# PKD.net
KiCad netlist of a schematic drawn in EAGLE
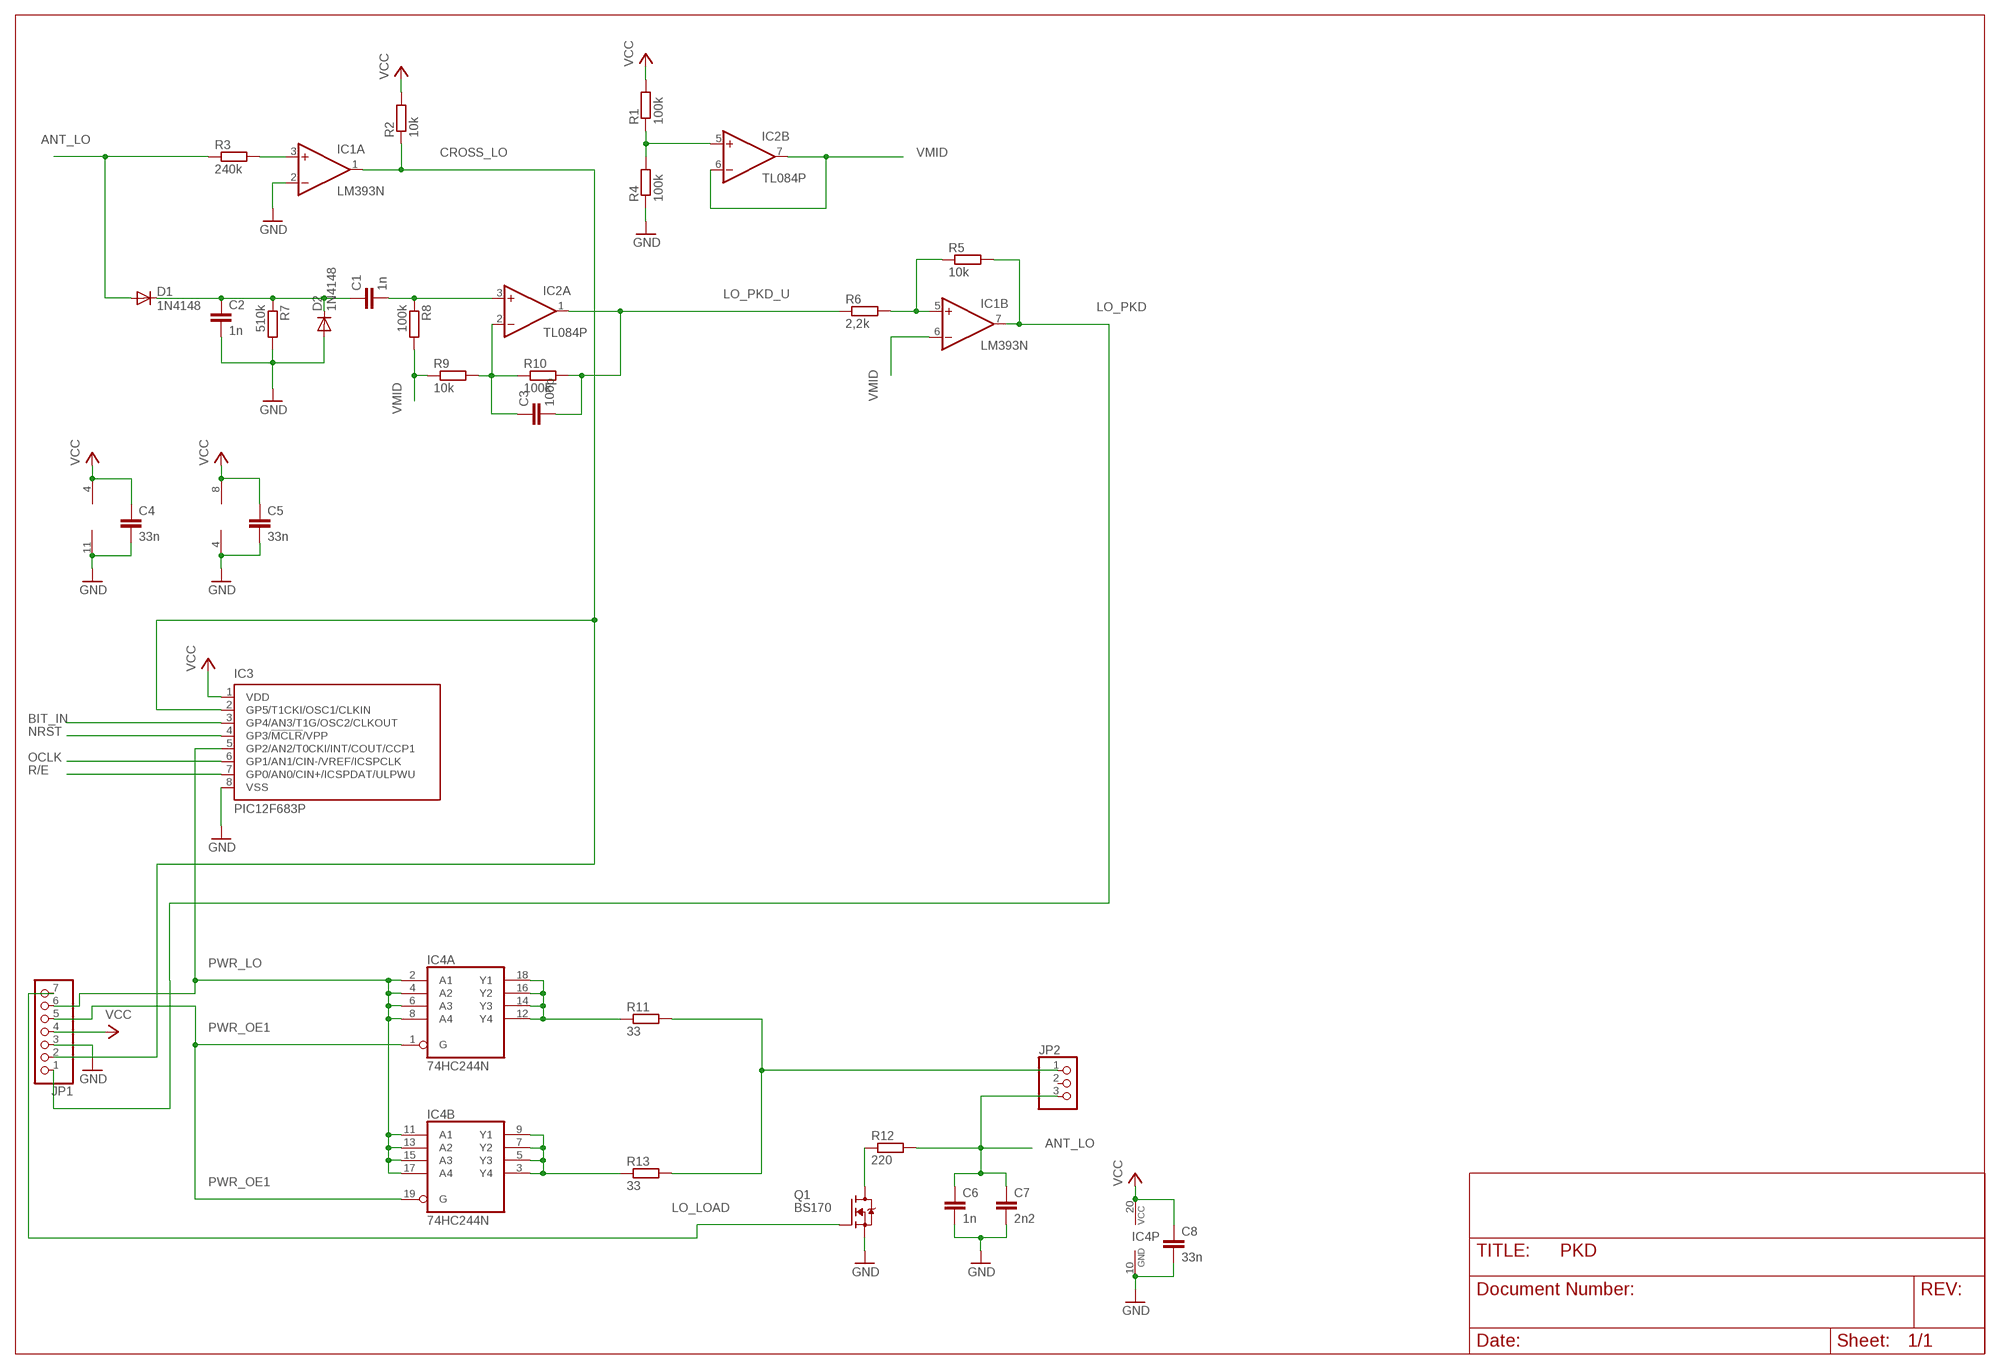
[diagram p0: schematic, sheet 1]

(export (version "E")
  (design (tool "Eeschema 10.0.6"))
  (components
    (comp (ref "C1")
      (value "1n")
      (footprint "eagle-import:C025-025X050")
      (libsource (lib "eagle-import") (part "C-EU025-025X050"))
    )
    (comp (ref "C2")
      (value "1n")
      (footprint "eagle-import:C050-030X075")
      (libsource (lib "eagle-import") (part "C-EU050-030X075"))
    )
    (comp (ref "C3")
      (value "100p")
      (footprint "eagle-import:C025-025X050")
      (libsource (lib "eagle-import") (part "C-EU025-025X050"))
    )
    (comp (ref "C4")
      (value "33n")
      (footprint "eagle-import:C025-025X050")
      (libsource (lib "eagle-import") (part "C-EU025-025X050"))
    )
    (comp (ref "C5")
      (value "33n")
      (footprint "eagle-import:C025-025X050")
      (libsource (lib "eagle-import") (part "C-EU025-025X050"))
    )
    (comp (ref "C6")
      (value "1n")
      (footprint "eagle-import:C025-025X050")
      (libsource (lib "eagle-import") (part "C-EU025-025X050"))
    )
    (comp (ref "C7")
      (value "2n2")
      (footprint "eagle-import:C025-025X050")
      (libsource (lib "eagle-import") (part "C-EU025-025X050"))
    )
    (comp (ref "C8")
      (value "33n")
      (footprint "eagle-import:C050-030X075")
      (libsource (lib "eagle-import") (part "C-EU050-030X075"))
    )
    (comp (ref "D1")
      (value "1N4148")
      (footprint "eagle-import:DO35-10")
      (libsource (lib "eagle-import") (part "1N4148DO35-10"))
    )
    (comp (ref "D2")
      (value "1N4148")
      (footprint "eagle-import:DO35-10")
      (libsource (lib "eagle-import") (part "1N4148DO35-10"))
    )
    (comp (ref "IC1")
      (value "LM393N")
      (footprint "eagle-import:DIL08")
      (libsource (lib "eagle-import") (part "LM393N"))
    )
    (comp (ref "IC2")
      (value "TL084P")
      (footprint "eagle-import:DIL14")
      (libsource (lib "eagle-import") (part "TL084P"))
    )
    (comp (ref "IC3")
      (value "PIC12F683P")
      (footprint "eagle-import:DIL8")
      (fields (field (name "MF") "MICROCHIP") (field (name "MPN") "PIC12F683-I/P"))
      (libsource (lib "eagle-import") (part "PIC12F683P"))
    )
    (comp (ref "IC4")
      (value "74HC244N")
      (footprint "eagle-import:DIL20")
      (libsource (lib "eagle-import") (part "74244NHC"))
    )
    (comp (ref "JP1")
      (value "PINHD-1X7")
      (footprint "eagle-import:1X07")
      (libsource (lib "eagle-import") (part "PINHD-1X7"))
    )
    (comp (ref "JP2")
      (value "PINHD-1X3/90")
      (footprint "eagle-import:1X03_90")
      (libsource (lib "eagle-import") (part "PINHD-1X3/90"))
    )
    (comp (ref "Q1")
      (value "BS170")
      (footprint "eagle-import:TO92-")
      (libsource (lib "eagle-import") (part "BS170"))
    )
    (comp (ref "R1")
      (value "100k")
      (footprint "eagle-import:0207_10")
      (libsource (lib "eagle-import") (part "R-EU_0207/10"))
    )
    (comp (ref "R2")
      (value "10k")
      (footprint "eagle-import:0207_10")
      (libsource (lib "eagle-import") (part "R-EU_0207/10"))
    )
    (comp (ref "R3")
      (value "240k")
      (footprint "eagle-import:0207_10")
      (libsource (lib "eagle-import") (part "R-EU_0207/10"))
    )
    (comp (ref "R4")
      (value "100k")
      (footprint "eagle-import:0207_10")
      (libsource (lib "eagle-import") (part "R-EU_0207/10"))
    )
    (comp (ref "R5")
      (value "10k")
      (footprint "eagle-import:0207_10")
      (libsource (lib "eagle-import") (part "R-EU_0207/10"))
    )
    (comp (ref "R6")
      (value "2,2k")
      (footprint "eagle-import:0207_10")
      (libsource (lib "eagle-import") (part "R-EU_0207/10"))
    )
    (comp (ref "R7")
      (value "510k")
      (footprint "eagle-import:0207_10")
      (libsource (lib "eagle-import") (part "R-EU_0207/10"))
    )
    (comp (ref "R8")
      (value "100k")
      (footprint "eagle-import:0207_10")
      (libsource (lib "eagle-import") (part "R-EU_0207/10"))
    )
    (comp (ref "R9")
      (value "10k")
      (footprint "eagle-import:0207_10")
      (libsource (lib "eagle-import") (part "R-EU_0207/10"))
    )
    (comp (ref "R10")
      (value "100k")
      (footprint "eagle-import:0207_10")
      (libsource (lib "eagle-import") (part "R-EU_0207/10"))
    )
    (comp (ref "R11")
      (value "33")
      (footprint "eagle-import:0207_10")
      (libsource (lib "eagle-import") (part "R-EU_0207/10"))
    )
    (comp (ref "R12")
      (value "220")
      (footprint "eagle-import:0207_10")
      (libsource (lib "eagle-import") (part "R-EU_0207/10"))
    )
    (comp (ref "R13")
      (value "33")
      (footprint "eagle-import:0207_10")
      (libsource (lib "eagle-import") (part "R-EU_0207/10"))
    )
  )
  (nets
    (net (code "1") (name "/ANT_LO") (class "Default")
      (node (ref "C6") (pin "1") (pinfunction "1_1") (pintype "passive"))
      (node (ref "C7") (pin "1") (pinfunction "1_1") (pintype "passive"))
      (node (ref "D1") (pin "A") (pinfunction "A_A") (pintype "passive"))
      (node (ref "JP2") (pin "3") (pinfunction "3_3") (pintype "passive"))
      (node (ref "R12") (pin "2") (pinfunction "2_2") (pintype "passive"))
      (node (ref "R3") (pin "1") (pinfunction "1_1") (pintype "passive"))
    )
    (net (code "2") (name "/BIT_IN") (class "Default")
      (node (ref "IC3") (pin "3") (pinfunction "GP4/AN3/T1G/OSC2/CLKOUT_3") (pintype "bidirectional"))
    )
    (net (code "3") (name "/CROSS_LO") (class "Default")
      (node (ref "IC1") (pin "1") (pinfunction "OUT_1") (pintype "output"))
      (node (ref "IC3") (pin "2") (pinfunction "GP5/T1CKI/OSC1/CLKIN_2") (pintype "bidirectional"))
      (node (ref "JP1") (pin "2") (pinfunction "2_2") (pintype "passive"))
      (node (ref "R2") (pin "1") (pinfunction "1_1") (pintype "passive"))
    )
    (net (code "4") (name "/LO_LOAD") (class "Default")
      (node (ref "JP1") (pin "7") (pinfunction "7_7") (pintype "passive"))
      (node (ref "Q1") (pin "2") (pinfunction "G_2") (pintype "passive"))
    )
    (net (code "5") (name "/LO_PKD") (class "Default")
      (node (ref "IC1") (pin "7") (pinfunction "OUT_7") (pintype "output"))
      (node (ref "JP1") (pin "1") (pinfunction "1_1") (pintype "passive"))
      (node (ref "R5") (pin "2") (pinfunction "2_2") (pintype "passive"))
    )
    (net (code "6") (name "/LO_PKD_U") (class "Default")
      (node (ref "C3") (pin "2") (pinfunction "2_2") (pintype "passive"))
      (node (ref "IC2") (pin "1") (pinfunction "OUT_1") (pintype "output"))
      (node (ref "R10") (pin "2") (pinfunction "2_2") (pintype "passive"))
      (node (ref "R6") (pin "1") (pinfunction "1_1") (pintype "passive"))
    )
    (net (code "7") (name "/NRST") (class "Default")
      (node (ref "IC3") (pin "4") (pinfunction "GP3/~{MCLR}/VPP_4") (pintype "bidirectional"))
    )
    (net (code "8") (name "/OCLK") (class "Default")
      (node (ref "IC3") (pin "6") (pinfunction "GP1/AN1/CIN-/VREF/ICSPCLK_6") (pintype "bidirectional"))
    )
    (net (code "9") (name "/PWR_LO") (class "Default")
      (node (ref "IC3") (pin "5") (pinfunction "GP2/AN2/T0CKI/INT/COUT/CCP1_5") (pintype "bidirectional"))
      (node (ref "IC4") (pin "11") (pinfunction "A1_11") (pintype "input"))
      (node (ref "IC4") (pin "13") (pinfunction "A2_13") (pintype "input"))
      (node (ref "IC4") (pin "15") (pinfunction "A3_15") (pintype "input"))
      (node (ref "IC4") (pin "17") (pinfunction "A4_17") (pintype "input"))
      (node (ref "IC4") (pin "2") (pinfunction "A1_2") (pintype "input"))
      (node (ref "IC4") (pin "4") (pinfunction "A2_4") (pintype "input"))
      (node (ref "IC4") (pin "6") (pinfunction "A3_6") (pintype "input"))
      (node (ref "IC4") (pin "8") (pinfunction "A4_8") (pintype "input"))
      (node (ref "JP1") (pin "6") (pinfunction "6_6") (pintype "passive"))
    )
    (net (code "10") (name "/PWR_OE1") (class "Default")
      (node (ref "IC4") (pin "1") (pinfunction "G_1") (pintype "input"))
      (node (ref "IC4") (pin "19") (pinfunction "G_19") (pintype "input"))
      (node (ref "JP1") (pin "5") (pinfunction "5_5") (pintype "passive"))
    )
    (net (code "11") (name "/R{slash}E") (class "Default")
      (node (ref "IC3") (pin "7") (pinfunction "GP0/AN0/CIN+/ICSPDAT/ULPWU_7") (pintype "bidirectional"))
    )
    (net (code "12") (name "/VMID") (class "Default")
      (node (ref "IC1") (pin "6") (pinfunction "-IN_6") (pintype "input"))
      (node (ref "IC2") (pin "6") (pinfunction "-IN_6") (pintype "input"))
      (node (ref "IC2") (pin "7") (pinfunction "OUT_7") (pintype "output"))
      (node (ref "R8") (pin "2") (pinfunction "2_2") (pintype "passive"))
      (node (ref "R9") (pin "1") (pinfunction "1_1") (pintype "passive"))
    )
    (net (code "13") (name "GND") (class "Default")
      (node (ref "C2") (pin "2") (pinfunction "2_2") (pintype "passive"))
      (node (ref "C4") (pin "2") (pinfunction "2_2") (pintype "passive"))
      (node (ref "C5") (pin "2") (pinfunction "2_2") (pintype "passive"))
      (node (ref "C6") (pin "2") (pinfunction "2_2") (pintype "passive"))
      (node (ref "C7") (pin "2") (pinfunction "2_2") (pintype "passive"))
      (node (ref "C8") (pin "2") (pinfunction "2_2") (pintype "passive"))
      (node (ref "D2") (pin "A") (pinfunction "A_A") (pintype "passive"))
      (node (ref "IC1") (pin "2") (pinfunction "-IN_2") (pintype "input"))
      (node (ref "IC1") (pin "4") (pinfunction "V-_4") (pintype "power_in"))
      (node (ref "IC2") (pin "11") (pinfunction "V-_11") (pintype "power_in"))
      (node (ref "IC3") (pin "8") (pinfunction "VSS_8") (pintype "power_in"))
      (node (ref "IC4") (pin "10") (pinfunction "GND_10") (pintype "power_in"))
      (node (ref "JP1") (pin "3") (pinfunction "3_3") (pintype "passive"))
      (node (ref "Q1") (pin "3") (pinfunction "S_3") (pintype "passive"))
      (node (ref "R4") (pin "1") (pinfunction "1_1") (pintype "passive"))
      (node (ref "R7") (pin "2") (pinfunction "2_2") (pintype "passive"))
    )
    (net (code "14") (name "Net-(C1-Pad1)") (class "Default")
      (node (ref "C1") (pin "1") (pinfunction "1_1") (pintype "passive"))
      (node (ref "C2") (pin "1") (pinfunction "1_1") (pintype "passive"))
      (node (ref "D1") (pin "C") (pinfunction "C_C") (pintype "passive"))
      (node (ref "D2") (pin "C") (pinfunction "C_C") (pintype "passive"))
      (node (ref "R7") (pin "1") (pinfunction "1_1") (pintype "passive"))
    )
    (net (code "15") (name "Net-(IC1A-+IN)") (class "Default")
      (node (ref "IC1") (pin "3") (pinfunction "+IN_3") (pintype "input"))
      (node (ref "R3") (pin "2") (pinfunction "2_2") (pintype "passive"))
    )
    (net (code "16") (name "Net-(IC1B-+IN)") (class "Default")
      (node (ref "IC1") (pin "5") (pinfunction "+IN_5") (pintype "input"))
      (node (ref "R5") (pin "1") (pinfunction "1_1") (pintype "passive"))
      (node (ref "R6") (pin "2") (pinfunction "2_2") (pintype "passive"))
    )
    (net (code "17") (name "Net-(IC2A-+IN)") (class "Default")
      (node (ref "C1") (pin "2") (pinfunction "2_2") (pintype "passive"))
      (node (ref "IC2") (pin "3") (pinfunction "+IN_3") (pintype "input"))
      (node (ref "R8") (pin "1") (pinfunction "1_1") (pintype "passive"))
    )
    (net (code "18") (name "Net-(IC2A--IN)") (class "Default")
      (node (ref "C3") (pin "1") (pinfunction "1_1") (pintype "passive"))
      (node (ref "IC2") (pin "2") (pinfunction "-IN_2") (pintype "input"))
      (node (ref "R10") (pin "1") (pinfunction "1_1") (pintype "passive"))
      (node (ref "R9") (pin "2") (pinfunction "2_2") (pintype "passive"))
    )
    (net (code "19") (name "Net-(IC2B-+IN)") (class "Default")
      (node (ref "IC2") (pin "5") (pinfunction "+IN_5") (pintype "input"))
      (node (ref "R1") (pin "1") (pinfunction "1_1") (pintype "passive"))
      (node (ref "R4") (pin "2") (pinfunction "2_2") (pintype "passive"))
    )
    (net (code "20") (name "Net-(IC4A-Y1)") (class "Default")
      (node (ref "IC4") (pin "12") (pinfunction "Y4_12") (pintype "tri_state"))
      (node (ref "IC4") (pin "14") (pinfunction "Y3_14") (pintype "tri_state"))
      (node (ref "IC4") (pin "16") (pinfunction "Y2_16") (pintype "tri_state"))
      (node (ref "IC4") (pin "18") (pinfunction "Y1_18") (pintype "tri_state"))
      (node (ref "R11") (pin "1") (pinfunction "1_1") (pintype "passive"))
    )
    (net (code "21") (name "Net-(IC4B-Y1)") (class "Default")
      (node (ref "IC4") (pin "3") (pinfunction "Y4_3") (pintype "tri_state"))
      (node (ref "IC4") (pin "5") (pinfunction "Y3_5") (pintype "tri_state"))
      (node (ref "IC4") (pin "7") (pinfunction "Y2_7") (pintype "tri_state"))
      (node (ref "IC4") (pin "9") (pinfunction "Y1_9") (pintype "tri_state"))
      (node (ref "R13") (pin "1") (pinfunction "1_1") (pintype "passive"))
    )
    (net (code "22") (name "Net-(JP2-Pad1)") (class "Default")
      (node (ref "JP2") (pin "1") (pinfunction "1_1") (pintype "passive"))
      (node (ref "R11") (pin "2") (pinfunction "2_2") (pintype "passive"))
      (node (ref "R13") (pin "2") (pinfunction "2_2") (pintype "passive"))
    )
    (net (code "23") (name "Net-(Q1-D)") (class "Default")
      (node (ref "Q1") (pin "1") (pinfunction "D_1") (pintype "passive"))
      (node (ref "R12") (pin "1") (pinfunction "1_1") (pintype "passive"))
    )
    (net (code "24") (name "VCC") (class "Default")
      (node (ref "C4") (pin "1") (pinfunction "1_1") (pintype "passive"))
      (node (ref "C5") (pin "1") (pinfunction "1_1") (pintype "passive"))
      (node (ref "C8") (pin "1") (pinfunction "1_1") (pintype "passive"))
      (node (ref "IC1") (pin "8") (pinfunction "V+_8") (pintype "power_in"))
      (node (ref "IC2") (pin "4") (pinfunction "V+_4") (pintype "power_in"))
      (node (ref "IC3") (pin "1") (pinfunction "VDD_1") (pintype "power_in"))
      (node (ref "IC4") (pin "20") (pinfunction "VCC_20") (pintype "power_in"))
      (node (ref "JP1") (pin "4") (pinfunction "4_4") (pintype "passive"))
      (node (ref "R1") (pin "2") (pinfunction "2_2") (pintype "passive"))
      (node (ref "R2") (pin "2") (pinfunction "2_2") (pintype "passive"))
    )
    (net (code "25") (name "unconnected-(JP2-Pad2)") (class "Default")
      (node (ref "JP2") (pin "2") (pinfunction "2_2") (pintype "passive"))
    )
  )
)
